# sang.net
KiCad netlist of a schematic drawn in EAGLE
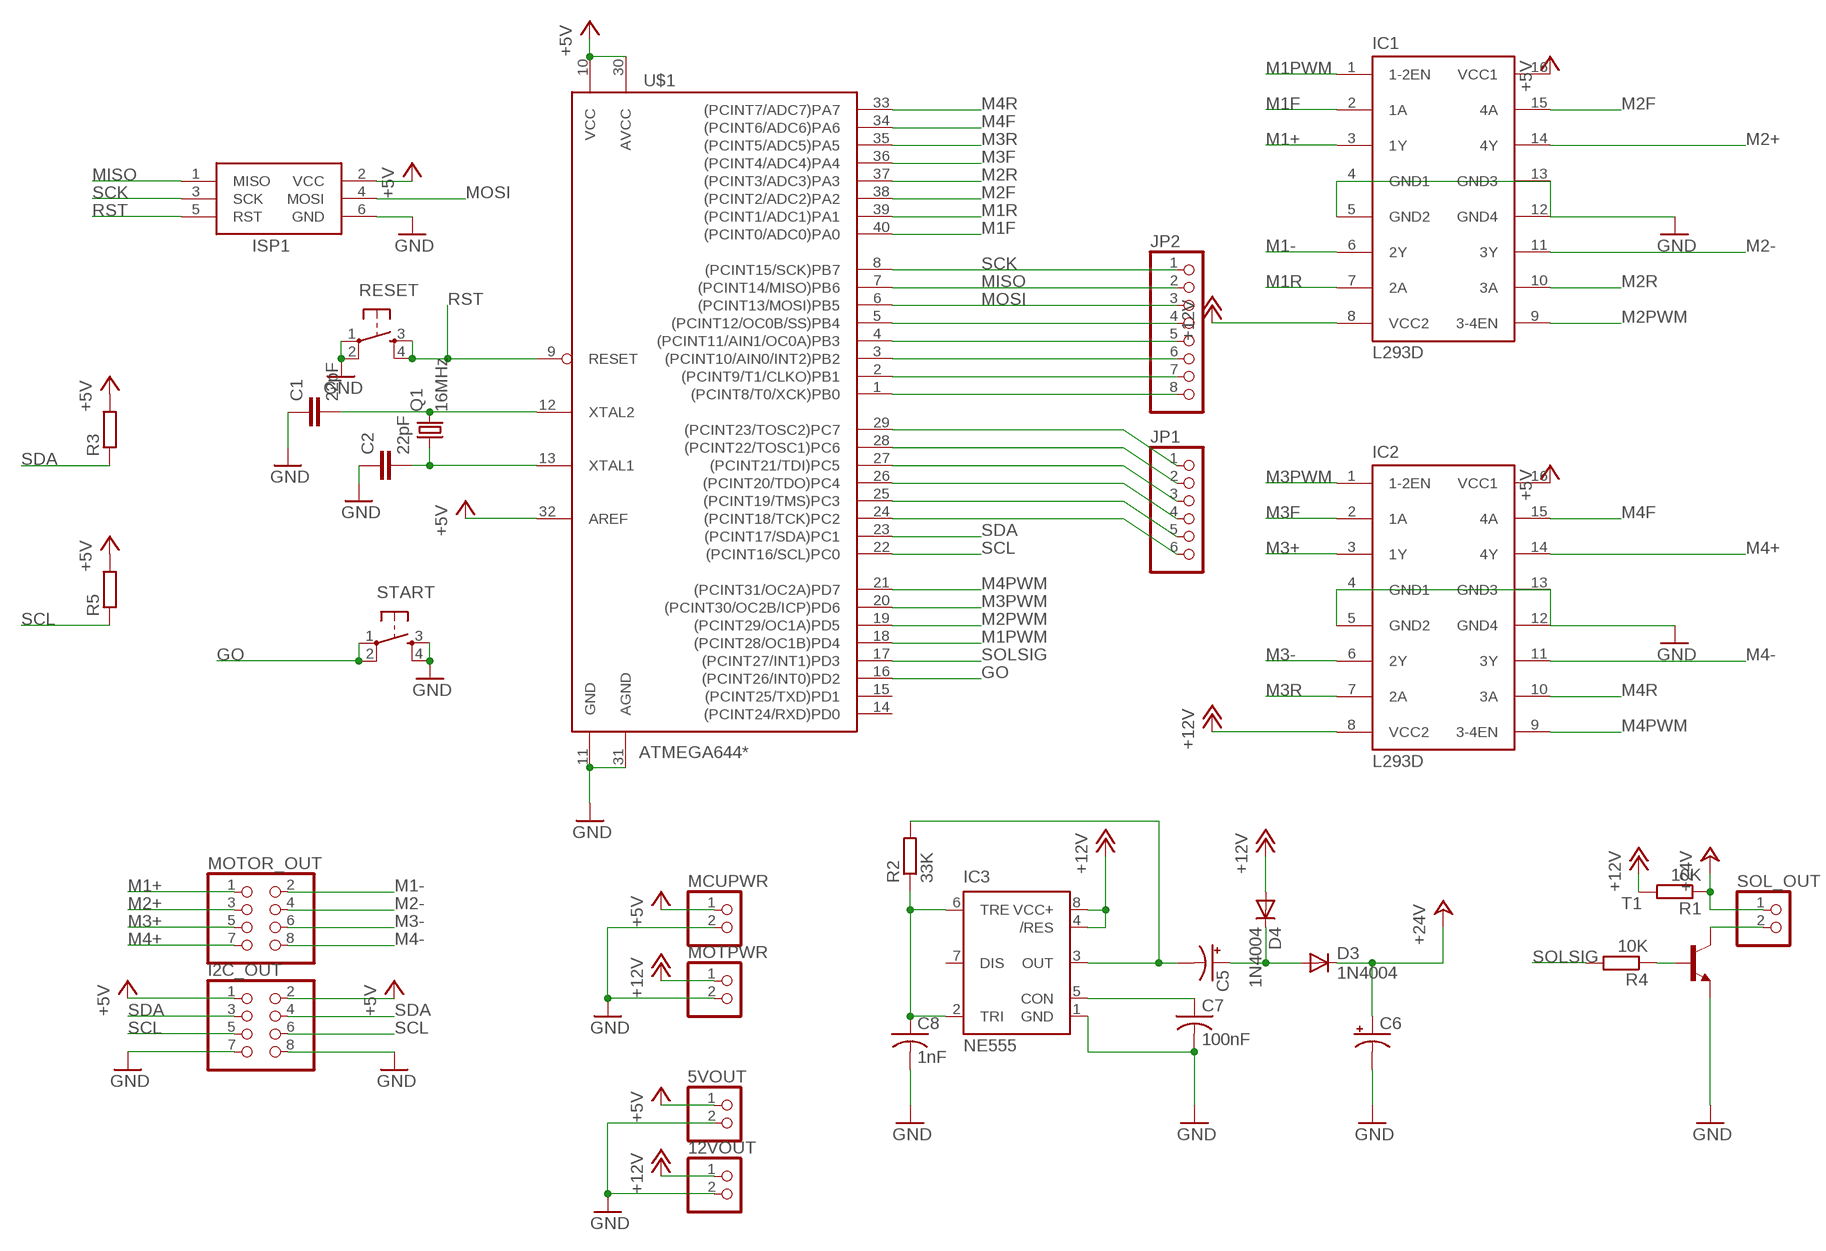
[diagram p0: schematic, sheet 1]

(export (version "E")
  (design (tool "Eeschema 10.0.6"))
  (components
    (comp (ref "5VOUT")
      (value "PINHD-1X2")
      (footprint "eagle-import:1X02")
      (libsource (lib "eagle-import") (part "PINHD-1X2"))
    )
    (comp (ref "12VOUT")
      (value "PINHD-1X2")
      (footprint "eagle-import:1X02")
      (libsource (lib "eagle-import") (part "PINHD-1X2"))
    )
    (comp (ref "C1")
      (value "22pF")
      (footprint "eagle-import:C2.5-2")
      (libsource (lib "eagle-import") (part "C2.5/2"))
    )
    (comp (ref "C2")
      (value "22pF")
      (footprint "eagle-import:C2.5-2")
      (libsource (lib "eagle-import") (part "C2.5/2"))
    )
    (comp (ref "C5")
      (value "CPOL-USE7.5-18")
      (footprint "eagle-import:E7,5-18")
      (libsource (lib "eagle-import") (part "CPOL-USE7.5-18"))
    )
    (comp (ref "C6")
      (value "CPOL-USE7.5-18")
      (footprint "eagle-import:E7,5-18")
      (libsource (lib "eagle-import") (part "CPOL-USE7.5-18"))
    )
    (comp (ref "C7")
      (value "100nF")
      (footprint "eagle-import:C025-030X050")
      (libsource (lib "eagle-import") (part "C-US025-030X050"))
    )
    (comp (ref "C8")
      (value "1nF")
      (footprint "eagle-import:C025-030X050")
      (libsource (lib "eagle-import") (part "C-US025-030X050"))
    )
    (comp (ref "D3")
      (value "1N4004")
      (footprint "eagle-import:DO41-10")
      (libsource (lib "eagle-import") (part "1N4004"))
    )
    (comp (ref "D4")
      (value "1N4004")
      (footprint "eagle-import:DO41-10")
      (libsource (lib "eagle-import") (part "1N4004"))
    )
    (comp (ref "I2C_OUT")
      (value "PINHD-2X4")
      (footprint "eagle-import:2X04")
      (libsource (lib "eagle-import") (part "PINHD-2X4"))
    )
    (comp (ref "IC1")
      (value "L293D")
      (footprint "eagle-import:DIL16")
      (libsource (lib "eagle-import") (part "L293D"))
    )
    (comp (ref "IC2")
      (value "L293D")
      (footprint "eagle-import:DIL16")
      (libsource (lib "eagle-import") (part "L293D"))
    )
    (comp (ref "IC3")
      (value "NE555")
      (footprint "eagle-import:DIL-08")
      (fields (field (name "MF") "Arrow Electronics") (field (name "MPN") "NE555N"))
      (libsource (lib "eagle-import") (part "NE555"))
    )
    (comp (ref "ISP1")
      (value "AVRISP-6")
      (footprint "eagle-import:AVRISP")
      (libsource (lib "eagle-import") (part "AVRISP-6"))
    )
    (comp (ref "JP1")
      (value "PINHD-1X6")
      (footprint "eagle-import:1X06")
      (libsource (lib "eagle-import") (part "PINHD-1X6"))
    )
    (comp (ref "JP2")
      (value "PINHD-1X8BIG")
      (footprint "eagle-import:1X08-BIG")
      (libsource (lib "eagle-import") (part "PINHD-1X8BIG"))
    )
    (comp (ref "MCUPWR")
      (value "PINHD-1X2")
      (footprint "eagle-import:1X02")
      (libsource (lib "eagle-import") (part "PINHD-1X2"))
    )
    (comp (ref "MOTOR_OUT")
      (value "PINHD-2X4")
      (footprint "eagle-import:2X04")
      (libsource (lib "eagle-import") (part "PINHD-2X4"))
    )
    (comp (ref "MOTPWR")
      (value "PINHD-1X2")
      (footprint "eagle-import:1X02")
      (libsource (lib "eagle-import") (part "PINHD-1X2"))
    )
    (comp (ref "Q1")
      (value "16MHz")
      (footprint "eagle-import:HC49U70")
      (libsource (lib "eagle-import") (part "CRYSTALHC49U70"))
    )
    (comp (ref "R1")
      (value "10K")
      (footprint "eagle-import:0207_10")
      (libsource (lib "eagle-import") (part "resistor_R-EU_0207/10"))
    )
    (comp (ref "R2")
      (value "33K")
      (footprint "eagle-import:0207_10")
      (libsource (lib "eagle-import") (part "R-EU_0207/10"))
    )
    (comp (ref "R3")
      (value "R-EU_0204/7")
      (footprint "eagle-import:0204_7")
      (libsource (lib "eagle-import") (part "resistor_R-EU_0204/7"))
    )
    (comp (ref "R4")
      (value "10K")
      (footprint "eagle-import:0207_10")
      (libsource (lib "eagle-import") (part "resistor_R-EU_0207/10"))
    )
    (comp (ref "R5")
      (value "R-EU_0204/7")
      (footprint "eagle-import:0204_7")
      (libsource (lib "eagle-import") (part "resistor_R-EU_0204/7"))
    )
    (comp (ref "RESET")
      (value "TAC_SWITCHPTH")
      (footprint "eagle-import:TACTILE-PTH")
      (libsource (lib "eagle-import") (part "TAC_SWITCHPTH"))
    )
    (comp (ref "SOL_OUT")
      (value "PINHD-1X2")
      (footprint "eagle-import:1X02")
      (libsource (lib "eagle-import") (part "PINHD-1X2"))
    )
    (comp (ref "START")
      (value "TAC_SWITCHPTH")
      (footprint "eagle-import:TACTILE-PTH")
      (libsource (lib "eagle-import") (part "TAC_SWITCHPTH"))
    )
    (comp (ref "T1")
      (value "2N2218-NPN-TO39-EBC")
      (footprint "eagle-import:TO39")
      (libsource (lib "eagle-import") (part "-NPN-TO39-EBC2N2218"))
    )
    (comp (ref "U$1")
      (value "ATMEGA644*")
      (footprint "eagle-import:ATMEGA644")
      (libsource (lib "eagle-import") (part "ATMEGA644"))
    )
  )
  (nets
    (net (code "1") (name "+5V") (class "Default")
      (node (ref "5VOUT") (pin "1") (pinfunction "1_1") (pintype "passive"))
      (node (ref "I2C_OUT") (pin "1") (pinfunction "1_1") (pintype "passive"))
      (node (ref "I2C_OUT") (pin "2") (pinfunction "2_2") (pintype "passive"))
      (node (ref "IC1") (pin "16") (pinfunction "VCC1_16") (pintype "power_in"))
      (node (ref "IC2") (pin "16") (pinfunction "VCC1_16") (pintype "power_in"))
      (node (ref "ISP1") (pin "2") (pinfunction "VCC_2") (pintype "power_in"))
      (node (ref "MCUPWR") (pin "1") (pinfunction "1_1") (pintype "passive"))
      (node (ref "R3") (pin "2") (pinfunction "2_2") (pintype "passive"))
      (node (ref "R5") (pin "2") (pinfunction "2_2") (pintype "passive"))
      (node (ref "U$1") (pin "10") (pinfunction "VCC_10") (pintype "power_in"))
      (node (ref "U$1") (pin "30") (pinfunction "AVCC_30") (pintype "power_in"))
      (node (ref "U$1") (pin "32") (pinfunction "AREF_32") (pintype "power_in"))
    )
    (net (code "2") (name "+12V") (class "Default")
      (node (ref "12VOUT") (pin "1") (pinfunction "1_1") (pintype "passive"))
      (node (ref "D4") (pin "A") (pinfunction "A_A") (pintype "passive"))
      (node (ref "IC1") (pin "8") (pinfunction "VCC2_8") (pintype "power_in"))
      (node (ref "IC2") (pin "8") (pinfunction "VCC2_8") (pintype "power_in"))
      (node (ref "IC3") (pin "4") (pinfunction "/RES_4") (pintype "input"))
      (node (ref "IC3") (pin "8") (pinfunction "VCC+_8") (pintype "power_in"))
      (node (ref "MOTPWR") (pin "1") (pinfunction "1_1") (pintype "passive"))
      (node (ref "R1") (pin "2") (pinfunction "2_2") (pintype "passive"))
    )
    (net (code "3") (name "+24V") (class "Default")
      (node (ref "C6") (pin "+") (pinfunction "+_+") (pintype "passive"))
      (node (ref "D3") (pin "C") (pinfunction "C_C") (pintype "passive"))
      (node (ref "R1") (pin "1") (pinfunction "1_1") (pintype "passive"))
      (node (ref "SOL_OUT") (pin "1") (pinfunction "1_1") (pintype "passive"))
    )
    (net (code "4") (name "/GO") (class "Default")
      (node (ref "START") (pin "1") (pinfunction "1_1") (pintype "passive"))
      (node (ref "START") (pin "2") (pinfunction "2_2") (pintype "passive"))
      (node (ref "U$1") (pin "16") (pinfunction "(PCINT26/INT0)PD2_16") (pintype "bidirectional"))
    )
    (net (code "5") (name "/M1+") (class "Default")
      (node (ref "IC1") (pin "3") (pinfunction "1Y_3") (pintype "output"))
      (node (ref "MOTOR_OUT") (pin "1") (pinfunction "1_1") (pintype "passive"))
    )
    (net (code "6") (name "/M1-") (class "Default")
      (node (ref "IC1") (pin "6") (pinfunction "2Y_6") (pintype "output"))
      (node (ref "MOTOR_OUT") (pin "2") (pinfunction "2_2") (pintype "passive"))
    )
    (net (code "7") (name "/M1F") (class "Default")
      (node (ref "IC1") (pin "2") (pinfunction "1A_2") (pintype "input"))
      (node (ref "U$1") (pin "40") (pinfunction "(PCINT0/ADC0)PA0_40") (pintype "bidirectional"))
    )
    (net (code "8") (name "/M1PWM") (class "Default")
      (node (ref "IC1") (pin "1") (pinfunction "1-2EN_1") (pintype "input"))
      (node (ref "U$1") (pin "18") (pinfunction "(PCINT28/OC1B)PD4_18") (pintype "bidirectional"))
    )
    (net (code "9") (name "/M1R") (class "Default")
      (node (ref "IC1") (pin "7") (pinfunction "2A_7") (pintype "input"))
      (node (ref "U$1") (pin "39") (pinfunction "(PCINT1/ADC1)PA1_39") (pintype "bidirectional"))
    )
    (net (code "10") (name "/M2+") (class "Default")
      (node (ref "IC1") (pin "14") (pinfunction "4Y_14") (pintype "output"))
      (node (ref "MOTOR_OUT") (pin "3") (pinfunction "3_3") (pintype "passive"))
    )
    (net (code "11") (name "/M2-") (class "Default")
      (node (ref "IC1") (pin "11") (pinfunction "3Y_11") (pintype "output"))
      (node (ref "MOTOR_OUT") (pin "4") (pinfunction "4_4") (pintype "passive"))
    )
    (net (code "12") (name "/M2F") (class "Default")
      (node (ref "IC1") (pin "15") (pinfunction "4A_15") (pintype "input"))
      (node (ref "U$1") (pin "38") (pinfunction "(PCINT2/ADC2)PA2_38") (pintype "bidirectional"))
    )
    (net (code "13") (name "/M2PWM") (class "Default")
      (node (ref "IC1") (pin "9") (pinfunction "3-4EN_9") (pintype "input"))
      (node (ref "U$1") (pin "19") (pinfunction "(PCINT29/OC1A)PD5_19") (pintype "bidirectional"))
    )
    (net (code "14") (name "/M2R") (class "Default")
      (node (ref "IC1") (pin "10") (pinfunction "3A_10") (pintype "input"))
      (node (ref "U$1") (pin "37") (pinfunction "(PCINT3/ADC3)PA3_37") (pintype "bidirectional"))
    )
    (net (code "15") (name "/M3+") (class "Default")
      (node (ref "IC2") (pin "3") (pinfunction "1Y_3") (pintype "output"))
      (node (ref "MOTOR_OUT") (pin "5") (pinfunction "5_5") (pintype "passive"))
    )
    (net (code "16") (name "/M3-") (class "Default")
      (node (ref "IC2") (pin "6") (pinfunction "2Y_6") (pintype "output"))
      (node (ref "MOTOR_OUT") (pin "6") (pinfunction "6_6") (pintype "passive"))
    )
    (net (code "17") (name "/M3F") (class "Default")
      (node (ref "IC2") (pin "2") (pinfunction "1A_2") (pintype "input"))
      (node (ref "U$1") (pin "36") (pinfunction "(PCINT4/ADC4)PA4_36") (pintype "bidirectional"))
    )
    (net (code "18") (name "/M3PWM") (class "Default")
      (node (ref "IC2") (pin "1") (pinfunction "1-2EN_1") (pintype "input"))
      (node (ref "U$1") (pin "20") (pinfunction "(PCINT30/OC2B/ICP)PD6_20") (pintype "bidirectional"))
    )
    (net (code "19") (name "/M3R") (class "Default")
      (node (ref "IC2") (pin "7") (pinfunction "2A_7") (pintype "input"))
      (node (ref "U$1") (pin "35") (pinfunction "(PCINT5/ADC5)PA5_35") (pintype "bidirectional"))
    )
    (net (code "20") (name "/M4+") (class "Default")
      (node (ref "IC2") (pin "14") (pinfunction "4Y_14") (pintype "output"))
      (node (ref "MOTOR_OUT") (pin "7") (pinfunction "7_7") (pintype "passive"))
    )
    (net (code "21") (name "/M4-") (class "Default")
      (node (ref "IC2") (pin "11") (pinfunction "3Y_11") (pintype "output"))
      (node (ref "MOTOR_OUT") (pin "8") (pinfunction "8_8") (pintype "passive"))
    )
    (net (code "22") (name "/M4F") (class "Default")
      (node (ref "IC2") (pin "15") (pinfunction "4A_15") (pintype "input"))
      (node (ref "U$1") (pin "34") (pinfunction "(PCINT6/ADC6)PA6_34") (pintype "bidirectional"))
    )
    (net (code "23") (name "/M4PWM") (class "Default")
      (node (ref "IC2") (pin "9") (pinfunction "3-4EN_9") (pintype "input"))
      (node (ref "U$1") (pin "21") (pinfunction "(PCINT31/OC2A)PD7_21") (pintype "bidirectional"))
    )
    (net (code "24") (name "/M4R") (class "Default")
      (node (ref "IC2") (pin "10") (pinfunction "3A_10") (pintype "input"))
      (node (ref "U$1") (pin "33") (pinfunction "(PCINT7/ADC7)PA7_33") (pintype "bidirectional"))
    )
    (net (code "25") (name "/MISO") (class "Default")
      (node (ref "ISP1") (pin "1") (pinfunction "MISO_1") (pintype "input"))
      (node (ref "JP2") (pin "2") (pinfunction "2_2") (pintype "passive"))
      (node (ref "U$1") (pin "7") (pinfunction "(PCINT14/MISO)PB6_7") (pintype "bidirectional"))
    )
    (net (code "26") (name "/MOSI") (class "Default")
      (node (ref "ISP1") (pin "4") (pinfunction "MOSI_4") (pintype "output"))
      (node (ref "JP2") (pin "3") (pinfunction "3_3") (pintype "passive"))
      (node (ref "U$1") (pin "6") (pinfunction "(PCINT13/MOSI)PB5_6") (pintype "bidirectional"))
    )
    (net (code "27") (name "/RST") (class "Default")
      (node (ref "ISP1") (pin "5") (pinfunction "RST_5") (pintype "output"))
      (node (ref "RESET") (pin "3") (pinfunction "3_3") (pintype "passive"))
      (node (ref "RESET") (pin "4") (pinfunction "4_4") (pintype "passive"))
      (node (ref "U$1") (pin "9") (pinfunction "RESET_9") (pintype "input"))
    )
    (net (code "28") (name "/SCK") (class "Default")
      (node (ref "ISP1") (pin "3") (pinfunction "SCK_3") (pintype "output"))
      (node (ref "JP2") (pin "1") (pinfunction "1_1") (pintype "passive"))
      (node (ref "U$1") (pin "8") (pinfunction "(PCINT15/SCK)PB7_8") (pintype "bidirectional"))
    )
    (net (code "29") (name "/SCL") (class "Default")
      (node (ref "I2C_OUT") (pin "5") (pinfunction "5_5") (pintype "passive"))
      (node (ref "I2C_OUT") (pin "6") (pinfunction "6_6") (pintype "passive"))
      (node (ref "R5") (pin "1") (pinfunction "1_1") (pintype "passive"))
      (node (ref "U$1") (pin "22") (pinfunction "(PCINT16/SCL)PC0_22") (pintype "bidirectional"))
    )
    (net (code "30") (name "/SDA") (class "Default")
      (node (ref "I2C_OUT") (pin "3") (pinfunction "3_3") (pintype "passive"))
      (node (ref "I2C_OUT") (pin "4") (pinfunction "4_4") (pintype "passive"))
      (node (ref "R3") (pin "1") (pinfunction "1_1") (pintype "passive"))
      (node (ref "U$1") (pin "23") (pinfunction "(PCINT17/SDA)PC1_23") (pintype "bidirectional"))
    )
    (net (code "31") (name "/SOLSIG") (class "Default")
      (node (ref "R4") (pin "2") (pinfunction "2_2") (pintype "passive"))
      (node (ref "U$1") (pin "17") (pinfunction "(PCINT27/INT1)PD3_17") (pintype "bidirectional"))
    )
    (net (code "32") (name "GND") (class "Default")
      (node (ref "12VOUT") (pin "2") (pinfunction "2_2") (pintype "passive"))
      (node (ref "5VOUT") (pin "2") (pinfunction "2_2") (pintype "passive"))
      (node (ref "C1") (pin "1") (pinfunction "1_1") (pintype "passive"))
      (node (ref "C2") (pin "1") (pinfunction "1_1") (pintype "passive"))
      (node (ref "C6") (pin "-") (pinfunction "-_-") (pintype "passive"))
      (node (ref "C7") (pin "2") (pinfunction "2_2") (pintype "passive"))
      (node (ref "C8") (pin "2") (pinfunction "2_2") (pintype "passive"))
      (node (ref "I2C_OUT") (pin "7") (pinfunction "7_7") (pintype "passive"))
      (node (ref "I2C_OUT") (pin "8") (pinfunction "8_8") (pintype "passive"))
      (node (ref "IC1") (pin "12") (pinfunction "GND4_12") (pintype "power_in"))
      (node (ref "IC1") (pin "13") (pinfunction "GND3_13") (pintype "power_in"))
      (node (ref "IC1") (pin "4") (pinfunction "GND1_4") (pintype "power_in"))
      (node (ref "IC1") (pin "5") (pinfunction "GND2_5") (pintype "power_in"))
      (node (ref "IC2") (pin "12") (pinfunction "GND4_12") (pintype "power_in"))
      (node (ref "IC2") (pin "13") (pinfunction "GND3_13") (pintype "power_in"))
      (node (ref "IC2") (pin "4") (pinfunction "GND1_4") (pintype "power_in"))
      (node (ref "IC2") (pin "5") (pinfunction "GND2_5") (pintype "power_in"))
      (node (ref "IC3") (pin "1") (pinfunction "GND_1") (pintype "power_in"))
      (node (ref "ISP1") (pin "6") (pinfunction "GND_6") (pintype "power_in"))
      (node (ref "MCUPWR") (pin "2") (pinfunction "2_2") (pintype "passive"))
      (node (ref "MOTPWR") (pin "2") (pinfunction "2_2") (pintype "passive"))
      (node (ref "RESET") (pin "1") (pinfunction "1_1") (pintype "passive"))
      (node (ref "RESET") (pin "2") (pinfunction "2_2") (pintype "passive"))
      (node (ref "START") (pin "3") (pinfunction "3_3") (pintype "passive"))
      (node (ref "START") (pin "4") (pinfunction "4_4") (pintype "passive"))
      (node (ref "T1") (pin "1") (pinfunction "E_1") (pintype "passive"))
      (node (ref "U$1") (pin "11") (pinfunction "GND_11") (pintype "power_in"))
      (node (ref "U$1") (pin "31") (pinfunction "AGND_31") (pintype "power_in"))
    )
    (net (code "33") (name "Net-(C5-Pad+)") (class "Default")
      (node (ref "C5") (pin "+") (pinfunction "+_+") (pintype "passive"))
      (node (ref "D3") (pin "A") (pinfunction "A_A") (pintype "passive"))
      (node (ref "D4") (pin "C") (pinfunction "C_C") (pintype "passive"))
    )
    (net (code "34") (name "Net-(IC3-CON)") (class "Default")
      (node (ref "C7") (pin "1") (pinfunction "1_1") (pintype "passive"))
      (node (ref "IC3") (pin "5") (pinfunction "CON_5") (pintype "input"))
    )
    (net (code "35") (name "Net-(IC3-OUT)") (class "Default")
      (node (ref "C5") (pin "-") (pinfunction "-_-") (pintype "passive"))
      (node (ref "IC3") (pin "3") (pinfunction "OUT_3") (pintype "output"))
      (node (ref "R2") (pin "2") (pinfunction "2_2") (pintype "passive"))
    )
    (net (code "36") (name "Net-(IC3-TRE)") (class "Default")
      (node (ref "C8") (pin "1") (pinfunction "1_1") (pintype "passive"))
      (node (ref "IC3") (pin "2") (pinfunction "TRI_2") (pintype "input"))
      (node (ref "IC3") (pin "6") (pinfunction "TRE_6") (pintype "input"))
      (node (ref "R2") (pin "1") (pinfunction "1_1") (pintype "passive"))
    )
    (net (code "37") (name "Net-(T1-B)") (class "Default")
      (node (ref "R4") (pin "1") (pinfunction "1_1") (pintype "passive"))
      (node (ref "T1") (pin "2") (pinfunction "B_2") (pintype "passive"))
    )
    (net (code "38") (name "Net-(T1-C)") (class "Default")
      (node (ref "SOL_OUT") (pin "2") (pinfunction "2_2") (pintype "passive"))
      (node (ref "T1") (pin "3") (pinfunction "C_3") (pintype "passive"))
    )
    (net (code "39") (name "Net-(U$1-(PCINT8{slash}T0{slash}XCK)PB0)") (class "Default")
      (node (ref "JP2") (pin "8") (pinfunction "8_8") (pintype "passive"))
      (node (ref "U$1") (pin "1") (pinfunction "(PCINT8/T0/XCK)PB0_1") (pintype "bidirectional"))
    )
    (net (code "40") (name "Net-(U$1-(PCINT9{slash}T1{slash}CLKO)PB1)") (class "Default")
      (node (ref "JP2") (pin "7") (pinfunction "7_7") (pintype "passive"))
      (node (ref "U$1") (pin "2") (pinfunction "(PCINT9/T1/CLKO)PB1_2") (pintype "bidirectional"))
    )
    (net (code "41") (name "Net-(U$1-(PCINT10{slash}AIN0{slash}INT2)PB2)") (class "Default")
      (node (ref "JP2") (pin "6") (pinfunction "6_6") (pintype "passive"))
      (node (ref "U$1") (pin "3") (pinfunction "(PCINT10/AIN0/INT2)PB2_3") (pintype "bidirectional"))
    )
    (net (code "42") (name "Net-(U$1-(PCINT11{slash}AIN1{slash}OC0A)PB3)") (class "Default")
      (node (ref "JP2") (pin "5") (pinfunction "5_5") (pintype "passive"))
      (node (ref "U$1") (pin "4") (pinfunction "(PCINT11/AIN1/OC0A)PB3_4") (pintype "bidirectional"))
    )
    (net (code "43") (name "Net-(U$1-(PCINT12{slash}OC0B{slash}SS)PB4)") (class "Default")
      (node (ref "JP2") (pin "4") (pinfunction "4_4") (pintype "passive"))
      (node (ref "U$1") (pin "5") (pinfunction "(PCINT12/OC0B/SS)PB4_5") (pintype "bidirectional"))
    )
    (net (code "44") (name "Net-(U$1-(PCINT18{slash}TCK)PC2)") (class "Default")
      (node (ref "JP1") (pin "6") (pinfunction "6_6") (pintype "passive"))
      (node (ref "U$1") (pin "24") (pinfunction "(PCINT18/TCK)PC2_24") (pintype "bidirectional"))
    )
    (net (code "45") (name "Net-(U$1-(PCINT19{slash}TMS)PC3)") (class "Default")
      (node (ref "JP1") (pin "5") (pinfunction "5_5") (pintype "passive"))
      (node (ref "U$1") (pin "25") (pinfunction "(PCINT19/TMS)PC3_25") (pintype "bidirectional"))
    )
    (net (code "46") (name "Net-(U$1-(PCINT20{slash}TDO)PC4)") (class "Default")
      (node (ref "JP1") (pin "4") (pinfunction "4_4") (pintype "passive"))
      (node (ref "U$1") (pin "26") (pinfunction "(PCINT20/TDO)PC4_26") (pintype "bidirectional"))
    )
    (net (code "47") (name "Net-(U$1-(PCINT21{slash}TDI)PC5)") (class "Default")
      (node (ref "JP1") (pin "3") (pinfunction "3_3") (pintype "passive"))
      (node (ref "U$1") (pin "27") (pinfunction "(PCINT21/TDI)PC5_27") (pintype "bidirectional"))
    )
    (net (code "48") (name "Net-(U$1-(PCINT22{slash}TOSC1)PC6)") (class "Default")
      (node (ref "JP1") (pin "2") (pinfunction "2_2") (pintype "passive"))
      (node (ref "U$1") (pin "28") (pinfunction "(PCINT22/TOSC1)PC6_28") (pintype "bidirectional"))
    )
    (net (code "49") (name "Net-(U$1-(PCINT23{slash}TOSC2)PC7)") (class "Default")
      (node (ref "JP1") (pin "1") (pinfunction "1_1") (pintype "passive"))
      (node (ref "U$1") (pin "29") (pinfunction "(PCINT23/TOSC2)PC7_29") (pintype "bidirectional"))
    )
    (net (code "50") (name "Net-(U$1-XTAL1)") (class "Default")
      (node (ref "C2") (pin "2") (pinfunction "2_2") (pintype "passive"))
      (node (ref "Q1") (pin "1") (pinfunction "1_1") (pintype "passive"))
      (node (ref "U$1") (pin "13") (pinfunction "XTAL1_13") (pintype "bidirectional"))
    )
    (net (code "51") (name "Net-(U$1-XTAL2)") (class "Default")
      (node (ref "C1") (pin "2") (pinfunction "2_2") (pintype "passive"))
      (node (ref "Q1") (pin "2") (pinfunction "2_2") (pintype "passive"))
      (node (ref "U$1") (pin "12") (pinfunction "XTAL2_12") (pintype "bidirectional"))
    )
    (net (code "52") (name "unconnected-(IC3-DIS-Pad7)") (class "Default")
      (node (ref "IC3") (pin "7") (pinfunction "DIS_7") (pintype "input"))
    )
    (net (code "53") (name "unconnected-(U$1-(PCINT24{slash}RXD)PD0-Pad14)") (class "Default")
      (node (ref "U$1") (pin "14") (pinfunction "(PCINT24/RXD)PD0_14") (pintype "bidirectional"))
    )
    (net (code "54") (name "unconnected-(U$1-(PCINT25{slash}TXD)PD1-Pad15)") (class "Default")
      (node (ref "U$1") (pin "15") (pinfunction "(PCINT25/TXD)PD1_15") (pintype "bidirectional"))
    )
  )
)
